# main.net
KiCad netlist of a schematic drawn in EAGLE
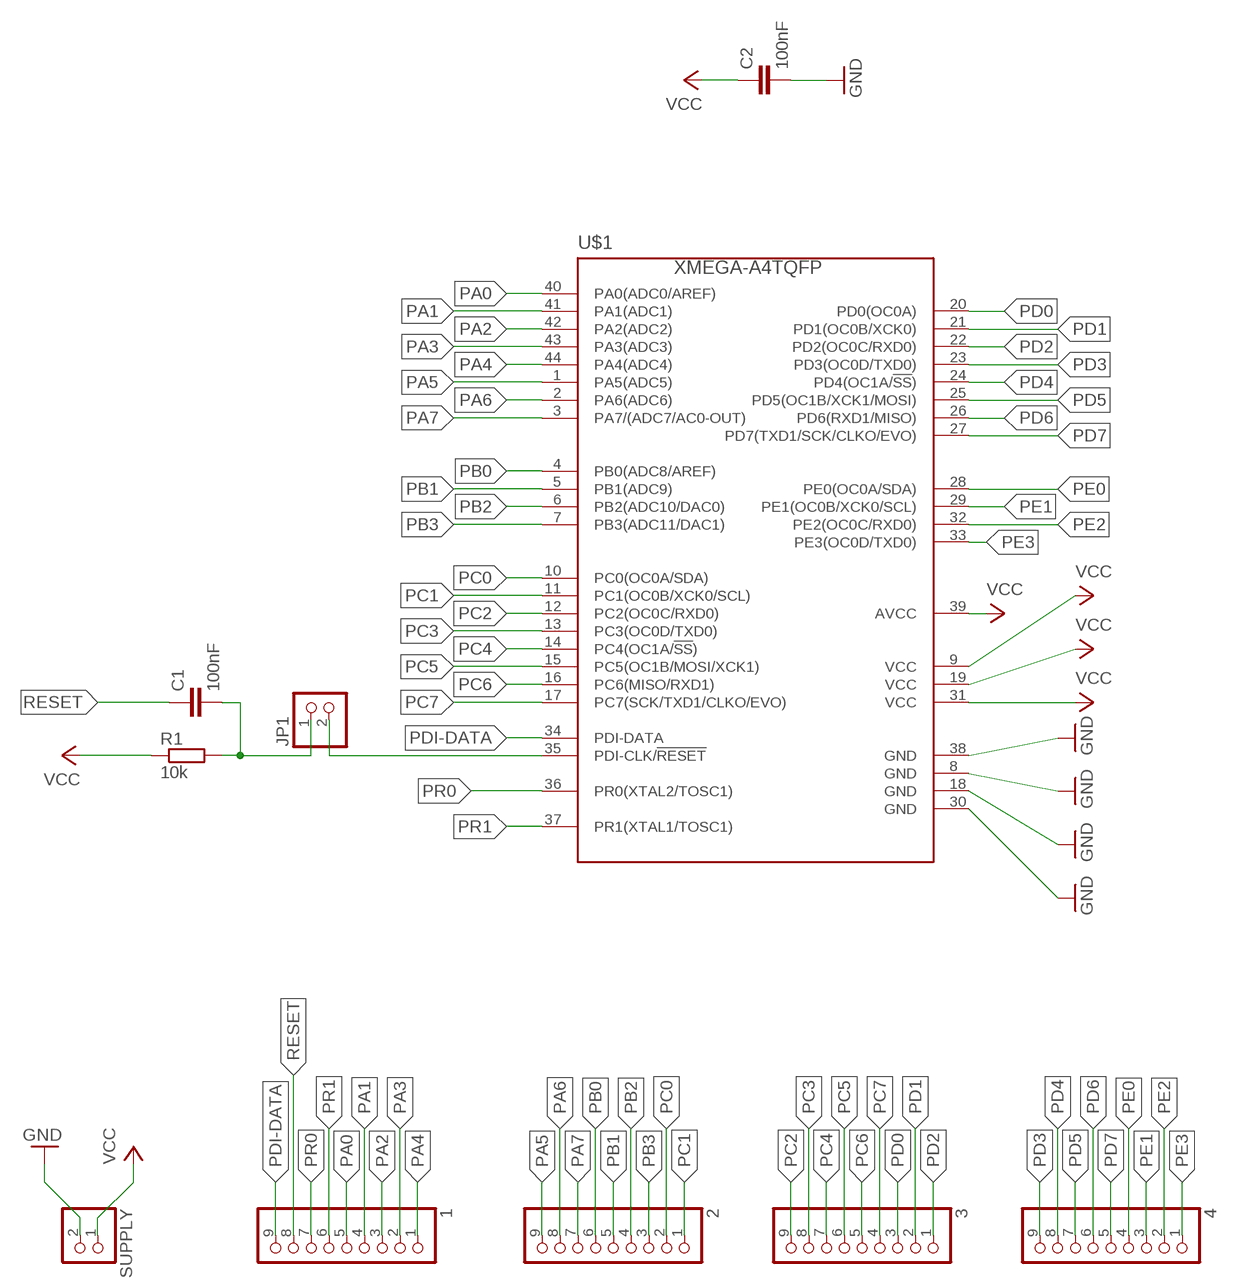
[diagram p0: schematic, sheet 1]

(export (version "E")
  (design (tool "Eeschema 10.0.6"))
  (components
    (comp (ref "1")
      (value "PINHD-1X9")
      (footprint "eagle-import:1X09")
      (libsource (lib "eagle-import") (part "PINHD-1X9"))
    )
    (comp (ref "2")
      (value "PINHD-1X9")
      (footprint "eagle-import:1X09")
      (libsource (lib "eagle-import") (part "PINHD-1X9"))
    )
    (comp (ref "3")
      (value "PINHD-1X9")
      (footprint "eagle-import:1X09")
      (libsource (lib "eagle-import") (part "PINHD-1X9"))
    )
    (comp (ref "4")
      (value "PINHD-1X9")
      (footprint "eagle-import:1X09")
      (libsource (lib "eagle-import") (part "PINHD-1X9"))
    )
    (comp (ref "C1")
      (value "100nF")
      (footprint "eagle-import:C0201")
      (libsource (lib "eagle-import") (part "CC0201"))
    )
    (comp (ref "C2")
      (value "100nF")
      (footprint "eagle-import:C0201")
      (libsource (lib "eagle-import") (part "CC0201"))
    )
    (comp (ref "JP1")
      (value "PINHD-1X2")
      (footprint "eagle-import:1X02")
      (libsource (lib "eagle-import") (part "PINHD-1X2"))
    )
    (comp (ref "R1")
      (value "10k")
      (footprint "eagle-import:R1206")
      (libsource (lib "eagle-import") (part "RR1206"))
    )
    (comp (ref "SUPPLY")
      (value "PINHD-1X2")
      (footprint "eagle-import:1X02")
      (libsource (lib "eagle-import") (part "PINHD-1X2"))
    )
    (comp (ref "U$1")
      (value "XMEGA-A4TQFP")
      (footprint "eagle-import:TQFP44")
      (libsource (lib "eagle-import") (part "XMEGA-A4TQFP"))
    )
  )
  (nets
    (net (code "1") (name "GND") (class "Default")
      (node (ref "C2") (pin "2") (pinfunction "2_2") (pintype "passive"))
      (node (ref "SUPPLY") (pin "2") (pinfunction "2_2") (pintype "passive"))
      (node (ref "U$1") (pin "18") (pinfunction "GND_18") (pintype "power_in"))
      (node (ref "U$1") (pin "30") (pinfunction "GND_30") (pintype "power_in"))
      (node (ref "U$1") (pin "38") (pinfunction "GND_38") (pintype "power_in"))
      (node (ref "U$1") (pin "8") (pinfunction "GND_8") (pintype "power_in"))
    )
    (net (code "2") (name "Net-(C1-Pad2)") (class "Default")
      (node (ref "C1") (pin "2") (pinfunction "2_2") (pintype "passive"))
      (node (ref "JP1") (pin "1") (pinfunction "1_1") (pintype "passive"))
      (node (ref "R1") (pin "2") (pinfunction "2_2") (pintype "passive"))
    )
    (net (code "3") (name "Net-(U$1-PDI-CLK{slash}~{RESET})") (class "Default")
      (node (ref "JP1") (pin "2") (pinfunction "2_2") (pintype "passive"))
      (node (ref "U$1") (pin "35") (pinfunction "PDI-CLK/~{RESET}_35") (pintype "input"))
    )
    (net (code "4") (name "PA0") (class "Default")
      (node (ref "1") (pin "5") (pinfunction "5_5") (pintype "passive"))
      (node (ref "U$1") (pin "40") (pinfunction "PA0(ADC0/AREF)_40") (pintype "bidirectional"))
    )
    (net (code "5") (name "PA1") (class "Default")
      (node (ref "1") (pin "4") (pinfunction "4_4") (pintype "passive"))
      (node (ref "U$1") (pin "41") (pinfunction "PA1(ADC1)_41") (pintype "bidirectional"))
    )
    (net (code "6") (name "PA2") (class "Default")
      (node (ref "1") (pin "3") (pinfunction "3_3") (pintype "passive"))
      (node (ref "U$1") (pin "42") (pinfunction "PA2(ADC2)_42") (pintype "bidirectional"))
    )
    (net (code "7") (name "PA3") (class "Default")
      (node (ref "1") (pin "2") (pinfunction "2_2") (pintype "passive"))
      (node (ref "U$1") (pin "43") (pinfunction "PA3(ADC3)_43") (pintype "bidirectional"))
    )
    (net (code "8") (name "PA4") (class "Default")
      (node (ref "1") (pin "1") (pinfunction "1_1") (pintype "passive"))
      (node (ref "U$1") (pin "44") (pinfunction "PA4(ADC4)_44") (pintype "bidirectional"))
    )
    (net (code "9") (name "PA5") (class "Default")
      (node (ref "2") (pin "9") (pinfunction "9_9") (pintype "passive"))
      (node (ref "U$1") (pin "1") (pinfunction "PA5(ADC5)_1") (pintype "bidirectional"))
    )
    (net (code "10") (name "PA6") (class "Default")
      (node (ref "2") (pin "8") (pinfunction "8_8") (pintype "passive"))
      (node (ref "U$1") (pin "2") (pinfunction "PA6(ADC6)_2") (pintype "bidirectional"))
    )
    (net (code "11") (name "PA7") (class "Default")
      (node (ref "2") (pin "7") (pinfunction "7_7") (pintype "passive"))
      (node (ref "U$1") (pin "3") (pinfunction "PA7/(ADC7/AC0-OUT)_3") (pintype "bidirectional"))
    )
    (net (code "12") (name "PB0") (class "Default")
      (node (ref "2") (pin "6") (pinfunction "6_6") (pintype "passive"))
      (node (ref "U$1") (pin "4") (pinfunction "PB0(ADC8/AREF)_4") (pintype "bidirectional"))
    )
    (net (code "13") (name "PB1") (class "Default")
      (node (ref "2") (pin "5") (pinfunction "5_5") (pintype "passive"))
      (node (ref "U$1") (pin "5") (pinfunction "PB1(ADC9)_5") (pintype "bidirectional"))
    )
    (net (code "14") (name "PB2") (class "Default")
      (node (ref "2") (pin "4") (pinfunction "4_4") (pintype "passive"))
      (node (ref "U$1") (pin "6") (pinfunction "PB2(ADC10/DAC0)_6") (pintype "bidirectional"))
    )
    (net (code "15") (name "PB3") (class "Default")
      (node (ref "2") (pin "3") (pinfunction "3_3") (pintype "passive"))
      (node (ref "U$1") (pin "7") (pinfunction "PB3(ADC11/DAC1)_7") (pintype "bidirectional"))
    )
    (net (code "16") (name "PC0") (class "Default")
      (node (ref "2") (pin "2") (pinfunction "2_2") (pintype "passive"))
      (node (ref "U$1") (pin "10") (pinfunction "PC0(OC0A/SDA)_10") (pintype "bidirectional"))
    )
    (net (code "17") (name "PC1") (class "Default")
      (node (ref "2") (pin "1") (pinfunction "1_1") (pintype "passive"))
      (node (ref "U$1") (pin "11") (pinfunction "PC1(OC0B/XCK0/SCL)_11") (pintype "bidirectional"))
    )
    (net (code "18") (name "PC2") (class "Default")
      (node (ref "3") (pin "9") (pinfunction "9_9") (pintype "passive"))
      (node (ref "U$1") (pin "12") (pinfunction "PC2(OC0C/RXD0)_12") (pintype "bidirectional"))
    )
    (net (code "19") (name "PC3") (class "Default")
      (node (ref "3") (pin "8") (pinfunction "8_8") (pintype "passive"))
      (node (ref "U$1") (pin "13") (pinfunction "PC3(OC0D/TXD0)_13") (pintype "bidirectional"))
    )
    (net (code "20") (name "PC4") (class "Default")
      (node (ref "3") (pin "7") (pinfunction "7_7") (pintype "passive"))
      (node (ref "U$1") (pin "14") (pinfunction "PC4(OC1A/~{SS})_14") (pintype "bidirectional"))
    )
    (net (code "21") (name "PC5") (class "Default")
      (node (ref "3") (pin "6") (pinfunction "6_6") (pintype "passive"))
      (node (ref "U$1") (pin "15") (pinfunction "PC5(OC1B/MOSI/XCK1)_15") (pintype "bidirectional"))
    )
    (net (code "22") (name "PC6") (class "Default")
      (node (ref "3") (pin "5") (pinfunction "5_5") (pintype "passive"))
      (node (ref "U$1") (pin "16") (pinfunction "PC6(MISO/RXD1)_16") (pintype "bidirectional"))
    )
    (net (code "23") (name "PC7") (class "Default")
      (node (ref "3") (pin "4") (pinfunction "4_4") (pintype "passive"))
      (node (ref "U$1") (pin "17") (pinfunction "PC7(SCK/TXD1/CLKO/EVO)_17") (pintype "bidirectional"))
    )
    (net (code "24") (name "PD0") (class "Default")
      (node (ref "3") (pin "3") (pinfunction "3_3") (pintype "passive"))
      (node (ref "U$1") (pin "20") (pinfunction "PD0(OC0A)_20") (pintype "bidirectional"))
    )
    (net (code "25") (name "PD1") (class "Default")
      (node (ref "3") (pin "2") (pinfunction "2_2") (pintype "passive"))
      (node (ref "U$1") (pin "21") (pinfunction "PD1(OC0B/XCK0)_21") (pintype "bidirectional"))
    )
    (net (code "26") (name "PD2") (class "Default")
      (node (ref "3") (pin "1") (pinfunction "1_1") (pintype "passive"))
      (node (ref "U$1") (pin "22") (pinfunction "PD2(OC0C/RXD0)_22") (pintype "bidirectional"))
    )
    (net (code "27") (name "PD3") (class "Default")
      (node (ref "4") (pin "9") (pinfunction "9_9") (pintype "passive"))
      (node (ref "U$1") (pin "23") (pinfunction "PD3(OC0D/TXD0)_23") (pintype "bidirectional"))
    )
    (net (code "28") (name "PD4") (class "Default")
      (node (ref "4") (pin "8") (pinfunction "8_8") (pintype "passive"))
      (node (ref "U$1") (pin "24") (pinfunction "PD4(OC1A/~{SS})_24") (pintype "bidirectional"))
    )
    (net (code "29") (name "PD5") (class "Default")
      (node (ref "4") (pin "7") (pinfunction "7_7") (pintype "passive"))
      (node (ref "U$1") (pin "25") (pinfunction "PD5(OC1B/XCK1/MOSI)_25") (pintype "bidirectional"))
    )
    (net (code "30") (name "PD6") (class "Default")
      (node (ref "4") (pin "6") (pinfunction "6_6") (pintype "passive"))
      (node (ref "U$1") (pin "26") (pinfunction "PD6(RXD1/MISO)_26") (pintype "bidirectional"))
    )
    (net (code "31") (name "PD7") (class "Default")
      (node (ref "4") (pin "5") (pinfunction "5_5") (pintype "passive"))
      (node (ref "U$1") (pin "27") (pinfunction "PD7(TXD1/SCK/CLKO/EVO)_27") (pintype "bidirectional"))
    )
    (net (code "32") (name "PDI-DATA") (class "Default")
      (node (ref "1") (pin "9") (pinfunction "9_9") (pintype "passive"))
      (node (ref "U$1") (pin "34") (pinfunction "PDI-DATA_34") (pintype "bidirectional"))
    )
    (net (code "33") (name "PE0") (class "Default")
      (node (ref "4") (pin "4") (pinfunction "4_4") (pintype "passive"))
      (node (ref "U$1") (pin "28") (pinfunction "PE0(OC0A/SDA)_28") (pintype "bidirectional"))
    )
    (net (code "34") (name "PE1") (class "Default")
      (node (ref "4") (pin "3") (pinfunction "3_3") (pintype "passive"))
      (node (ref "U$1") (pin "29") (pinfunction "PE1(OC0B/XCK0/SCL)_29") (pintype "bidirectional"))
    )
    (net (code "35") (name "PE2") (class "Default")
      (node (ref "4") (pin "2") (pinfunction "2_2") (pintype "passive"))
      (node (ref "U$1") (pin "32") (pinfunction "PE2(OC0C/RXD0)_32") (pintype "bidirectional"))
    )
    (net (code "36") (name "PE3") (class "Default")
      (node (ref "4") (pin "1") (pinfunction "1_1") (pintype "passive"))
      (node (ref "U$1") (pin "33") (pinfunction "PE3(OC0D/TXD0)_33") (pintype "bidirectional"))
    )
    (net (code "37") (name "PR0") (class "Default")
      (node (ref "1") (pin "7") (pinfunction "7_7") (pintype "passive"))
      (node (ref "U$1") (pin "36") (pinfunction "PR0(XTAL2/TOSC1)_36") (pintype "bidirectional"))
    )
    (net (code "38") (name "PR1") (class "Default")
      (node (ref "1") (pin "6") (pinfunction "6_6") (pintype "passive"))
      (node (ref "U$1") (pin "37") (pinfunction "PR1(XTAL1/TOSC1)_37") (pintype "bidirectional"))
    )
    (net (code "39") (name "RESET") (class "Default")
      (node (ref "1") (pin "8") (pinfunction "8_8") (pintype "passive"))
      (node (ref "C1") (pin "1") (pinfunction "1_1") (pintype "passive"))
    )
    (net (code "40") (name "VCC") (class "Default")
      (node (ref "C2") (pin "1") (pinfunction "1_1") (pintype "passive"))
      (node (ref "R1") (pin "1") (pinfunction "1_1") (pintype "passive"))
      (node (ref "SUPPLY") (pin "1") (pinfunction "1_1") (pintype "passive"))
      (node (ref "U$1") (pin "19") (pinfunction "VCC_19") (pintype "power_in"))
      (node (ref "U$1") (pin "31") (pinfunction "VCC_31") (pintype "power_in"))
      (node (ref "U$1") (pin "39") (pinfunction "AVCC_39") (pintype "power_in"))
      (node (ref "U$1") (pin "9") (pinfunction "VCC_9") (pintype "power_in"))
    )
  )
)
